# DE-290817_02.net
KiCad netlist of a schematic drawn in Altium Designer
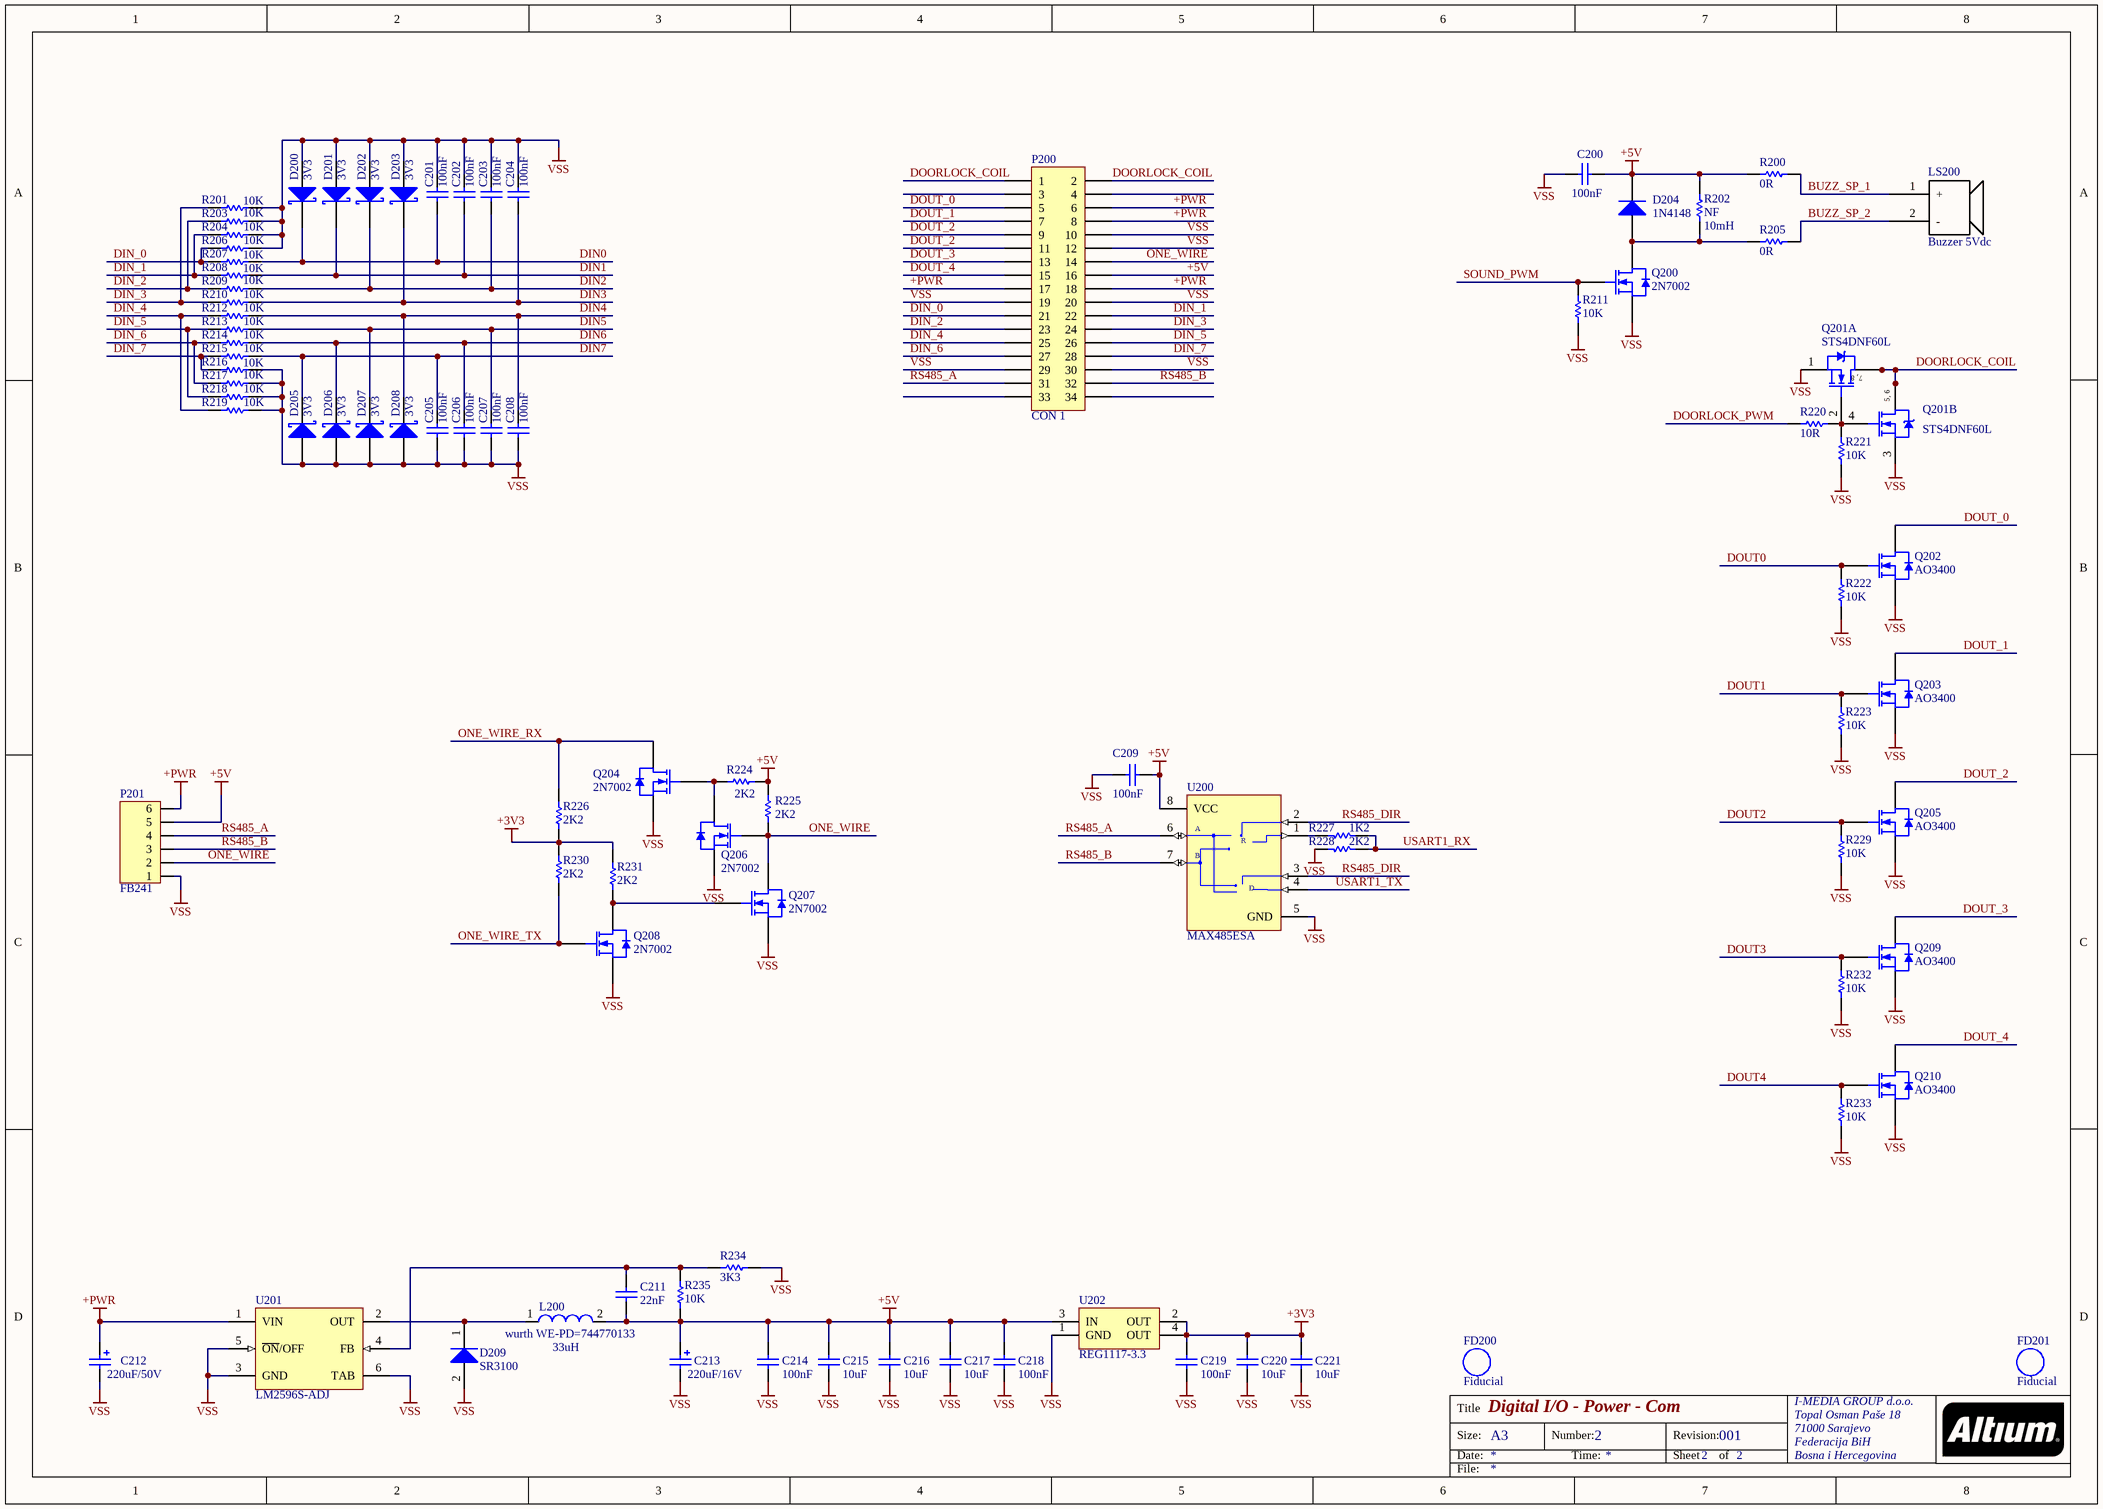
[diagram p0: DE-290817_02.SchDoc]

(export (version "E")
  (design (tool "Eeschema 10.0.6"))
  (components
    (comp (ref "C200")
      (value "100nF")
      (footprint "0603")
      (description "Ceramic Chip Capacitor - Standard")
      (fields (field (name "PUBLISHER") "Altium Limited"))
      (libsource (lib "DE-251215") (part "C0603"))
    )
    (comp (ref "C201")
      (value "100nF")
      (footprint "0603")
      (description "Ceramic Chip Capacitor - Standard")
      (fields (field (name "PUBLISHER") "Altium Limited"))
      (libsource (lib "DE-251215") (part "C0603"))
    )
    (comp (ref "C202")
      (value "100nF")
      (footprint "0603")
      (description "Ceramic Chip Capacitor - Standard")
      (fields (field (name "PUBLISHER") "Altium Limited"))
      (libsource (lib "DE-251215") (part "C0603"))
    )
    (comp (ref "C203")
      (value "100nF")
      (footprint "0603")
      (description "Ceramic Chip Capacitor - Standard")
      (fields (field (name "PUBLISHER") "Altium Limited"))
      (libsource (lib "DE-251215") (part "C0603"))
    )
    (comp (ref "C204")
      (value "100nF")
      (footprint "0603")
      (description "Ceramic Chip Capacitor - Standard")
      (fields (field (name "PUBLISHER") "Altium Limited"))
      (libsource (lib "DE-251215") (part "C0603"))
    )
    (comp (ref "C205")
      (value "100nF")
      (footprint "0603")
      (description "Ceramic Chip Capacitor - Standard")
      (fields (field (name "PUBLISHER") "Altium Limited"))
      (libsource (lib "DE-251215") (part "C0603"))
    )
    (comp (ref "C206")
      (value "100nF")
      (footprint "0603")
      (description "Ceramic Chip Capacitor - Standard")
      (fields (field (name "PUBLISHER") "Altium Limited"))
      (libsource (lib "DE-251215") (part "C0603"))
    )
    (comp (ref "C207")
      (value "100nF")
      (footprint "0603")
      (description "Ceramic Chip Capacitor - Standard")
      (fields (field (name "PUBLISHER") "Altium Limited"))
      (libsource (lib "DE-251215") (part "C0603"))
    )
    (comp (ref "C208")
      (value "100nF")
      (footprint "0603")
      (description "Ceramic Chip Capacitor - Standard")
      (fields (field (name "PUBLISHER") "Altium Limited"))
      (libsource (lib "DE-251215") (part "C0603"))
    )
    (comp (ref "C209")
      (value "100nF")
      (footprint "0603")
      (description "Ceramic Chip Capacitor - Standard")
      (fields (field (name "PUBLISHER") "Altium Limited"))
      (libsource (lib "DE-251215") (part "C0603"))
    )
    (comp (ref "C211")
      (value "22nF")
      (footprint "0603")
      (description "Ceramic Chip Capacitor - Standard")
      (fields (field (name "PUBLISHER") "Altium Limited"))
      (libsource (lib "DE-251215") (part "C0603"))
    )
    (comp (ref "C212")
      (value "220uF/50V")
      (footprint "EEEHA1H101P")
      (description "Aluminum Electrolytic Capacitors (SMD Type)")
      (libsource (lib "DE-290817") (part "EEEHA1H101P"))
    )
    (comp (ref "C213")
      (value "220uF/16V")
      (footprint "EEEHA1H101P")
      (description "Aluminum Electrolytic Capacitors (SMD Type)")
      (libsource (lib "DE-290817") (part "EEEHA1C221P"))
    )
    (comp (ref "C214")
      (value "100nF")
      (footprint "0603")
      (description "Ceramic Chip Capacitor - Standard")
      (fields (field (name "PUBLISHER") "Altium Limited"))
      (libsource (lib "DE-251215") (part "C0603"))
    )
    (comp (ref "C215")
      (value "10uF")
      (footprint "0805")
      (description "Ceramic Chip Capacitor - Standard")
      (fields (field (name "PUBLISHER") "Altium Limited"))
      (libsource (lib "DE-251215") (part "C0805"))
    )
    (comp (ref "C216")
      (value "10uF")
      (footprint "0805")
      (description "Ceramic Chip Capacitor - Standard")
      (fields (field (name "PUBLISHER") "Altium Limited"))
      (libsource (lib "DE-251215") (part "C0805"))
    )
    (comp (ref "C217")
      (value "10uF")
      (footprint "0805")
      (description "Ceramic Chip Capacitor - Standard")
      (fields (field (name "PUBLISHER") "Altium Limited"))
      (libsource (lib "DE-251215") (part "C0805"))
    )
    (comp (ref "C218")
      (value "100nF")
      (footprint "0603")
      (description "Ceramic Chip Capacitor - Standard")
      (fields (field (name "PUBLISHER") "Altium Limited"))
      (libsource (lib "DE-251215") (part "C0603"))
    )
    (comp (ref "C219")
      (value "100nF")
      (footprint "0603")
      (description "Ceramic Chip Capacitor - Standard")
      (fields (field (name "PUBLISHER") "Altium Limited"))
      (libsource (lib "DE-251215") (part "C0603"))
    )
    (comp (ref "C220")
      (value "10uF")
      (footprint "0805")
      (description "Ceramic Chip Capacitor - Standard")
      (fields (field (name "PUBLISHER") "Altium Limited"))
      (libsource (lib "DE-251215") (part "C0805"))
    )
    (comp (ref "C221")
      (value "10uF")
      (footprint "0805")
      (description "Ceramic Chip Capacitor - Standard")
      (fields (field (name "PUBLISHER") "Altium Limited"))
      (libsource (lib "DE-251215") (part "C0805"))
    )
    (comp (ref "D200")
      (value "3V3")
      (footprint "SOD323")
      (description "Schottky Barrier Diode")
      (fields (field (name "PUBLISHER") "Altium Limited"))
      (libsource (lib "DE-290817") (part "1PS76SB10"))
    )
    (comp (ref "D201")
      (value "3V3")
      (footprint "SOD323")
      (description "Schottky Barrier Diode")
      (fields (field (name "PUBLISHER") "Altium Limited"))
      (libsource (lib "DE-290817") (part "1PS76SB10"))
    )
    (comp (ref "D202")
      (value "3V3")
      (footprint "SOD323")
      (description "Schottky Barrier Diode")
      (fields (field (name "PUBLISHER") "Altium Limited"))
      (libsource (lib "DE-290817") (part "1PS76SB10"))
    )
    (comp (ref "D203")
      (value "3V3")
      (footprint "SOD323")
      (description "Schottky Barrier Diode")
      (fields (field (name "PUBLISHER") "Altium Limited"))
      (libsource (lib "DE-290817") (part "1PS76SB10"))
    )
    (comp (ref "D204")
      (value "1N4148")
      (footprint "SOD323")
      (description "General-purpose Diode")
      (fields (field (name "PUBLISHER") "Altium Limited"))
      (libsource (lib "DE-200216_01") (part "BAS321"))
    )
    (comp (ref "D205")
      (value "3V3")
      (footprint "SOD323")
      (description "Schottky Barrier Diode")
      (fields (field (name "PUBLISHER") "Altium Limited"))
      (libsource (lib "DE-290817") (part "1PS76SB10"))
    )
    (comp (ref "D206")
      (value "3V3")
      (footprint "SOD323")
      (description "Schottky Barrier Diode")
      (fields (field (name "PUBLISHER") "Altium Limited"))
      (libsource (lib "DE-290817") (part "1PS76SB10"))
    )
    (comp (ref "D207")
      (value "3V3")
      (footprint "SOD323")
      (description "Schottky Barrier Diode")
      (fields (field (name "PUBLISHER") "Altium Limited"))
      (libsource (lib "DE-290817") (part "1PS76SB10"))
    )
    (comp (ref "D208")
      (value "3V3")
      (footprint "SOD323")
      (description "Schottky Barrier Diode")
      (fields (field (name "PUBLISHER") "Altium Limited"))
      (libsource (lib "DE-290817") (part "1PS76SB10"))
    )
    (comp (ref "D209")
      (value "SR3100")
      (footprint "ONSC-SMA-2-403D-02_C_V")
      (description "Schottky Power Rectifier, 2-Pin SMA, Pb-Free, Tape and Reel")
      (fields (field (name "MANUFACTURER") "On Semiconductor") (field (name "PARTNUMBER") "MBRA320T3G"))
      (libsource (lib "ON Semi Schottky Diodes & Schottky Rectifiers") (part "MBRA320T3G"))
    )
    (comp (ref "FD200")
      (value "Fiducial")
      (footprint "Fiducial")
      (description "Fiduchial mark")
      (libsource (lib "DE-200216_02_1") (part "Fiduchial"))
    )
    (comp (ref "FD201")
      (value "Fiducial")
      (footprint "Fiducial")
      (description "Fiduchial mark")
      (libsource (lib "DE-200216_02_1") (part "Fiduchial"))
    )
    (comp (ref "L200")
      (value "wurth WE-PD=744770133")
      (footprint "WE-PD-XL")
      (description "SMD-Shielded Power Inductor WE-PD, L = 33 µH")
      (fields (field (name "PARTNUMBER") "744770133") (field (name "ALTIUM_VALUE") "33uH"))
      (libsource (lib "WE-PD SMD Shielded Power Inductor") (part "744770133"))
    )
    (comp (ref "LS200")
      (value "Buzzer 5Vdc")
      (footprint "BUZZER")
      (description "5Vdc PCB buzzer")
      (libsource (lib "DE-290817") (part "BUZZER"))
    )
    (comp (ref "P200")
      (value "CON 1")
      (footprint "HDR2X17")
      (description "Header, 17-Pin, Dual row")
      (fields (field (name "PUBLISHER") "Altium Limited"))
      (libsource (lib "Miscellaneous Connectors") (part "Header 17X2"))
    )
    (comp (ref "P201")
      (value "FB241")
      (footprint "FB241_6")
      (description "PCB MOUNT TERMINAL BLOCK 2.5MM PITCH")
      (libsource (lib "DE-290817") (part "TERMINAL BLOCK 6"))
    )
    (comp (ref "Q200")
      (value "2N7002")
      (footprint "SOT23_N")
      (description "N-channel Enhancement Mode Field-effect Transistor")
      (fields (field (name "PUBLISHER") "Altium Limited"))
      (libsource (lib "Philips Discrete MOSFET - Low Power") (part "2N7002"))
    )
    (comp (ref "Q201")
      (value "STS4DNF60L")
      (footprint "ONSC-SOIC-8-751-07_V")
      (description "Power MOSFET, 40 V, 5.8 A, Dual N-Channel, 8-Pin SOIC, Pb-Free, Tape and Reel")
      (fields (field (name "MANUFACTURER") "On Semiconductor") (field (name "PARTNUMBER") "NVMD6N04R2G"))
      (libsource (lib "ON Semi MOSFETs") (part "NVMD6N04R2G"))
    )
    (comp (ref "Q202")
      (value "AO3400")
      (footprint "SOT23_N")
      (description "N-channel Enhancement Mode Field-effect Transistor")
      (fields (field (name "PUBLISHER") "Altium Limited"))
      (libsource (lib "Philips Discrete MOSFET - Low Power") (part "2N7002"))
    )
    (comp (ref "Q203")
      (value "AO3400")
      (footprint "SOT23_N")
      (description "N-channel Enhancement Mode Field-effect Transistor")
      (fields (field (name "PUBLISHER") "Altium Limited"))
      (libsource (lib "Philips Discrete MOSFET - Low Power") (part "2N7002"))
    )
    (comp (ref "Q204")
      (value "2N7002")
      (footprint "SOT23_N")
      (description "N-channel Enhancement Mode Vertical D-MOSFET")
      (fields (field (name "PUBLISHER") "Altium Limited"))
      (libsource (lib "DE-290817") (part "BSS123"))
    )
    (comp (ref "Q205")
      (value "AO3400")
      (footprint "SOT23_N")
      (description "N-channel Enhancement Mode Field-effect Transistor")
      (fields (field (name "PUBLISHER") "Altium Limited"))
      (libsource (lib "Philips Discrete MOSFET - Low Power") (part "2N7002"))
    )
    (comp (ref "Q206")
      (value "2N7002")
      (footprint "SOT23_N")
      (description "N-channel Enhancement Mode Vertical D-MOSFET")
      (fields (field (name "PUBLISHER") "Altium Limited"))
      (libsource (lib "DE-290817") (part "BSS123"))
    )
    (comp (ref "Q207")
      (value "2N7002")
      (footprint "SOT23_N")
      (description "N-channel Enhancement Mode Vertical D-MOSFET")
      (fields (field (name "PUBLISHER") "Altium Limited"))
      (libsource (lib "DE-290817") (part "BSS123"))
    )
    (comp (ref "Q208")
      (value "2N7002")
      (footprint "SOT23_N")
      (description "N-channel Enhancement Mode Vertical D-MOSFET")
      (fields (field (name "PUBLISHER") "Altium Limited"))
      (libsource (lib "DE-290817") (part "BSS123"))
    )
    (comp (ref "Q209")
      (value "AO3400")
      (footprint "SOT23_N")
      (description "N-channel Enhancement Mode Field-effect Transistor")
      (fields (field (name "PUBLISHER") "Altium Limited"))
      (libsource (lib "Philips Discrete MOSFET - Low Power") (part "2N7002"))
    )
    (comp (ref "Q210")
      (value "AO3400")
      (footprint "SOT23_N")
      (description "N-channel Enhancement Mode Field-effect Transistor")
      (fields (field (name "PUBLISHER") "Altium Limited"))
      (libsource (lib "Philips Discrete MOSFET - Low Power") (part "2N7002"))
    )
    (comp (ref "R200")
      (value "0R")
      (footprint "ERA-0603")
      (fields (field (name "PUBLISHER") "Altium Limited"))
      (libsource (lib "DE-200216_03") (part "ERAV"))
    )
    (comp (ref "R201")
      (value "10K")
      (footprint "ERA-0603")
      (fields (field (name "PUBLISHER") "Altium Limited"))
      (libsource (lib "DE-200216_03") (part "ERAV"))
    )
    (comp (ref "R202")
      (value "NF")
      (footprint "RD3.2x1.7")
      (fields (field (name "ALTIUM_VALUE") "10mH") (field (name "PUBLISHER") "Altium Limited"))
      (libsource (lib "Panasonic Resistor") (part "ERD6FC"))
    )
    (comp (ref "R203")
      (value "10K")
      (footprint "ERA-0603")
      (fields (field (name "PUBLISHER") "Altium Limited"))
      (libsource (lib "DE-200216_03") (part "ERAV"))
    )
    (comp (ref "R204")
      (value "10K")
      (footprint "ERA-0603")
      (fields (field (name "PUBLISHER") "Altium Limited"))
      (libsource (lib "DE-251215") (part "ERAV"))
    )
    (comp (ref "R205")
      (value "0R")
      (footprint "ERA-0603")
      (fields (field (name "PUBLISHER") "Altium Limited"))
      (libsource (lib "DE-200216_03") (part "ERAV"))
    )
    (comp (ref "R206")
      (value "10K")
      (footprint "ERA-0603")
      (fields (field (name "PUBLISHER") "Altium Limited"))
      (libsource (lib "DE-251215") (part "ERAV"))
    )
    (comp (ref "R207")
      (value "10K")
      (footprint "ERA-0603")
      (fields (field (name "PUBLISHER") "Altium Limited"))
      (libsource (lib "DE-200216_03") (part "ERAV"))
    )
    (comp (ref "R208")
      (value "10K")
      (footprint "ERA-0603")
      (fields (field (name "PUBLISHER") "Altium Limited"))
      (libsource (lib "DE-200216_03") (part "ERAV"))
    )
    (comp (ref "R209")
      (value "10K")
      (footprint "ERA-0603")
      (fields (field (name "PUBLISHER") "Altium Limited"))
      (libsource (lib "DE-200216_03") (part "ERAV"))
    )
    (comp (ref "R210")
      (value "10K")
      (footprint "ERA-0603")
      (fields (field (name "PUBLISHER") "Altium Limited"))
      (libsource (lib "DE-251215") (part "ERAV"))
    )
    (comp (ref "R211")
      (value "10K")
      (footprint "ERA-0603")
      (fields (field (name "PUBLISHER") "Altium Limited"))
      (libsource (lib "DE-200216_03") (part "ERAV"))
    )
    (comp (ref "R212")
      (value "10K")
      (footprint "ERA-0603")
      (fields (field (name "PUBLISHER") "Altium Limited"))
      (libsource (lib "DE-251215") (part "ERAV"))
    )
    (comp (ref "R213")
      (value "10K")
      (footprint "ERA-0603")
      (fields (field (name "PUBLISHER") "Altium Limited"))
      (libsource (lib "DE-251215") (part "ERAV"))
    )
    (comp (ref "R214")
      (value "10K")
      (footprint "ERA-0603")
      (fields (field (name "PUBLISHER") "Altium Limited"))
      (libsource (lib "DE-251215") (part "ERAV"))
    )
    (comp (ref "R215")
      (value "10K")
      (footprint "ERA-0603")
      (fields (field (name "PUBLISHER") "Altium Limited"))
      (libsource (lib "DE-251215") (part "ERAV"))
    )
    (comp (ref "R216")
      (value "10K")
      (footprint "ERA-0603")
      (fields (field (name "PUBLISHER") "Altium Limited"))
      (libsource (lib "DE-200216_03") (part "ERAV"))
    )
    (comp (ref "R217")
      (value "10K")
      (footprint "ERA-0603")
      (fields (field (name "PUBLISHER") "Altium Limited"))
      (libsource (lib "DE-200216_03") (part "ERAV"))
    )
    (comp (ref "R218")
      (value "10K")
      (footprint "ERA-0603")
      (fields (field (name "PUBLISHER") "Altium Limited"))
      (libsource (lib "DE-251215") (part "ERAV"))
    )
    (comp (ref "R219")
      (value "10K")
      (footprint "ERA-0603")
      (fields (field (name "PUBLISHER") "Altium Limited"))
      (libsource (lib "DE-251215") (part "ERAV"))
    )
    (comp (ref "R220")
      (value "10R")
      (footprint "ERA-0603")
      (fields (field (name "PUBLISHER") "Altium Limited"))
      (libsource (lib "DE-200216_03") (part "ERAV"))
    )
    (comp (ref "R221")
      (value "10K")
      (footprint "ERA-0603")
      (fields (field (name "PUBLISHER") "Altium Limited"))
      (libsource (lib "DE-200216_03") (part "ERAV"))
    )
    (comp (ref "R222")
      (value "10K")
      (footprint "ERA-0603")
      (fields (field (name "PUBLISHER") "Altium Limited"))
      (libsource (lib "DE-200216_03") (part "ERAV"))
    )
    (comp (ref "R223")
      (value "10K")
      (footprint "ERA-0603")
      (fields (field (name "PUBLISHER") "Altium Limited"))
      (libsource (lib "DE-200216_03") (part "ERAV"))
    )
    (comp (ref "R224")
      (value "2K2")
      (footprint "ERA-0603")
      (fields (field (name "PUBLISHER") "Altium Limited"))
      (libsource (lib "DE-200216_03") (part "ERAV"))
    )
    (comp (ref "R225")
      (value "2K2")
      (footprint "ERA-0603")
      (fields (field (name "PUBLISHER") "Altium Limited"))
      (libsource (lib "DE-200216_03") (part "ERAV"))
    )
    (comp (ref "R226")
      (value "2K2")
      (footprint "ERA-0603")
      (fields (field (name "PUBLISHER") "Altium Limited"))
      (libsource (lib "DE-290817") (part "ERAV"))
    )
    (comp (ref "R227")
      (value "1K2")
      (footprint "ERA-0603")
      (fields (field (name "PUBLISHER") "Altium Limited"))
      (libsource (lib "DE-200216_03") (part "ERAV"))
    )
    (comp (ref "R228")
      (value "2K2")
      (footprint "ERA-0603")
      (fields (field (name "PUBLISHER") "Altium Limited"))
      (libsource (lib "DE-200216_03") (part "ERAV"))
    )
    (comp (ref "R229")
      (value "10K")
      (footprint "ERA-0603")
      (fields (field (name "PUBLISHER") "Altium Limited"))
      (libsource (lib "DE-200216_03") (part "ERAV"))
    )
    (comp (ref "R230")
      (value "2K2")
      (footprint "ERA-0603")
      (fields (field (name "PUBLISHER") "Altium Limited"))
      (libsource (lib "DE-200216_03") (part "ERAV"))
    )
    (comp (ref "R231")
      (value "2K2")
      (footprint "ERA-0603")
      (fields (field (name "PUBLISHER") "Altium Limited"))
      (libsource (lib "DE-200216_03") (part "ERAV"))
    )
    (comp (ref "R232")
      (value "10K")
      (footprint "ERA-0603")
      (fields (field (name "PUBLISHER") "Altium Limited"))
      (libsource (lib "DE-200216_03") (part "ERAV"))
    )
    (comp (ref "R233")
      (value "10K")
      (footprint "ERA-0603")
      (fields (field (name "PUBLISHER") "Altium Limited"))
      (libsource (lib "DE-200216_03") (part "ERAV"))
    )
    (comp (ref "R234")
      (value "3K3")
      (footprint "ERA-0603")
      (fields (field (name "PUBLISHER") "Altium Limited"))
      (libsource (lib "DE-251215") (part "ERAV"))
    )
    (comp (ref "R235")
      (value "10K")
      (footprint "ERA-0603")
      (fields (field (name "PUBLISHER") "Altium Limited"))
      (libsource (lib "DE-251215") (part "ERAV"))
    )
    (comp (ref "U200")
      (value "MAX485ESA")
      (footprint "NSO8_M")
      (description "Low-Power, Slew-Rate-Limited RS-485/RS-422 Transceiver")
      (fields (field (name "PUBLISHER") "Altium Limited"))
      (libsource (lib "Maxim Communication Transceiver") (part "MAX485ESA"))
    )
    (comp (ref "U201")
      (value "LM2596S-ADJ")
      (footprint "TS5B_N")
      (description "SIMPLE SWITCHER® Power Converter 150 KHz 3A Step-Down Voltage Regulator, 5-pin TO-263")
      (fields (field (name "MANUFACTURER") "National Semiconductor"))
      (libsource (lib "National Semiconductor Switcher") (part "LM2596S-ADJ"))
    )
    (comp (ref "U202")
      (value "REG1117-3.3")
      (footprint "ZZ311")
      (description "800mA and 1A Low Dropout Positive Regulator 2.85V, 3.3V, 5V, and Adjustable")
      (fields (field (name "PUBLISHER") "Altium Limited"))
      (libsource (lib "DE-251215") (part "REG1117-3.3"))
    )
  )
  (nets
    (net (code "1") (name "+3V3") (class "Default")
      (node (ref "C219") (pin "2") (pinfunction "2_2") (pintype "passive"))
      (node (ref "C220") (pin "2") (pinfunction "2_2") (pintype "passive"))
      (node (ref "C221") (pin "2") (pinfunction "2_2") (pintype "passive"))
      (node (ref "R226") (pin "1") (pinfunction "1_1") (pintype "passive"))
      (node (ref "R230") (pin "2") (pinfunction "2_2") (pintype "passive"))
      (node (ref "R231") (pin "2") (pinfunction "2_2") (pintype "passive"))
      (node (ref "U202") (pin "2") (pinfunction "OUT_2") (pintype "power_in"))
      (node (ref "U202") (pin "4") (pinfunction "OUT_4") (pintype "power_in"))
    )
    (net (code "2") (name "+5V") (class "Default")
      (node (ref "C200") (pin "1") (pinfunction "1_1") (pintype "passive"))
      (node (ref "C209") (pin "2") (pinfunction "2_2") (pintype "passive"))
      (node (ref "C211") (pin "1") (pinfunction "1_1") (pintype "passive"))
      (node (ref "C213") (pin "1") (pinfunction "1_1") (pintype "passive"))
      (node (ref "C214") (pin "2") (pinfunction "2_2") (pintype "passive"))
      (node (ref "C215") (pin "2") (pinfunction "2_2") (pintype "passive"))
      (node (ref "C216") (pin "2") (pinfunction "2_2") (pintype "passive"))
      (node (ref "C217") (pin "2") (pinfunction "2_2") (pintype "passive"))
      (node (ref "C218") (pin "2") (pinfunction "2_2") (pintype "passive"))
      (node (ref "D204") (pin "1") (pinfunction "K_1") (pintype "passive"))
      (node (ref "L200") (pin "2") (pinfunction "2_2") (pintype "passive"))
      (node (ref "P200") (pin "16") (pinfunction "16_16") (pintype "passive"))
      (node (ref "P201") (pin "5") (pinfunction "5_5") (pintype "passive"))
      (node (ref "R200") (pin "2") (pinfunction "2_2") (pintype "passive"))
      (node (ref "R202") (pin "2") (pinfunction "2_2") (pintype "passive"))
      (node (ref "R224") (pin "1") (pinfunction "1_1") (pintype "passive"))
      (node (ref "R225") (pin "2") (pinfunction "2_2") (pintype "passive"))
      (node (ref "R235") (pin "2") (pinfunction "2_2") (pintype "passive"))
      (node (ref "U200") (pin "8") (pinfunction "VCC_8") (pintype "power_in"))
      (node (ref "U202") (pin "3") (pinfunction "IN_3") (pintype "power_in"))
    )
    (net (code "3") (name "+PWR") (class "Default")
      (node (ref "C212") (pin "1") (pinfunction "1_1") (pintype "passive"))
      (node (ref "P200") (pin "17") (pinfunction "17_17") (pintype "passive"))
      (node (ref "P200") (pin "18") (pinfunction "18_18") (pintype "passive"))
      (node (ref "P200") (pin "6") (pinfunction "6_6") (pintype "passive"))
      (node (ref "P200") (pin "8") (pinfunction "8_8") (pintype "passive"))
      (node (ref "P201") (pin "6") (pinfunction "6_6") (pintype "passive"))
      (node (ref "U201") (pin "1") (pinfunction "VIN_1") (pintype "power_in"))
    )
    (net (code "4") (name "/BUZZ_SP_1") (class "Default")
      (node (ref "LS200") (pin "1") (pinfunction "+_1") (pintype "passive"))
      (node (ref "R200") (pin "1") (pinfunction "1_1") (pintype "passive"))
    )
    (net (code "5") (name "/BUZZ_SP_2") (class "Default")
      (node (ref "LS200") (pin "2") (pinfunction "-_2") (pintype "passive"))
      (node (ref "R205") (pin "1") (pinfunction "1_1") (pintype "passive"))
    )
    (net (code "6") (name "/DIN0") (class "Default")
      (node (ref "C201") (pin "2") (pinfunction "2_2") (pintype "passive"))
      (node (ref "D200") (pin "1") (pinfunction "K_1") (pintype "passive"))
      (node (ref "R207") (pin "2") (pinfunction "2_2") (pintype "passive"))
    )
    (net (code "7") (name "/DIN1") (class "Default")
      (node (ref "C202") (pin "2") (pinfunction "2_2") (pintype "passive"))
      (node (ref "D201") (pin "1") (pinfunction "K_1") (pintype "passive"))
      (node (ref "R208") (pin "2") (pinfunction "2_2") (pintype "passive"))
    )
    (net (code "8") (name "/DIN2") (class "Default")
      (node (ref "C203") (pin "2") (pinfunction "2_2") (pintype "passive"))
      (node (ref "D202") (pin "1") (pinfunction "K_1") (pintype "passive"))
      (node (ref "R209") (pin "2") (pinfunction "2_2") (pintype "passive"))
    )
    (net (code "9") (name "/DIN3") (class "Default")
      (node (ref "C204") (pin "2") (pinfunction "2_2") (pintype "passive"))
      (node (ref "D203") (pin "1") (pinfunction "K_1") (pintype "passive"))
      (node (ref "R210") (pin "2") (pinfunction "2_2") (pintype "passive"))
    )
    (net (code "10") (name "/DIN4") (class "Default")
      (node (ref "C208") (pin "2") (pinfunction "2_2") (pintype "passive"))
      (node (ref "D208") (pin "1") (pinfunction "K_1") (pintype "passive"))
      (node (ref "R212") (pin "2") (pinfunction "2_2") (pintype "passive"))
    )
    (net (code "11") (name "/DIN5") (class "Default")
      (node (ref "C207") (pin "2") (pinfunction "2_2") (pintype "passive"))
      (node (ref "D207") (pin "1") (pinfunction "K_1") (pintype "passive"))
      (node (ref "R213") (pin "2") (pinfunction "2_2") (pintype "passive"))
    )
    (net (code "12") (name "/DIN6") (class "Default")
      (node (ref "C206") (pin "2") (pinfunction "2_2") (pintype "passive"))
      (node (ref "D206") (pin "1") (pinfunction "K_1") (pintype "passive"))
      (node (ref "R214") (pin "2") (pinfunction "2_2") (pintype "passive"))
    )
    (net (code "13") (name "/DIN7") (class "Default")
      (node (ref "C205") (pin "2") (pinfunction "2_2") (pintype "passive"))
      (node (ref "D205") (pin "1") (pinfunction "K_1") (pintype "passive"))
      (node (ref "R215") (pin "2") (pinfunction "2_2") (pintype "passive"))
    )
    (net (code "14") (name "/DIN_0") (class "Default")
      (node (ref "P200") (pin "21") (pinfunction "21_21") (pintype "passive"))
      (node (ref "R206") (pin "1") (pinfunction "1_1") (pintype "passive"))
      (node (ref "R207") (pin "1") (pinfunction "1_1") (pintype "passive"))
    )
    (net (code "15") (name "/DIN_1") (class "Default")
      (node (ref "P200") (pin "22") (pinfunction "22_22") (pintype "passive"))
      (node (ref "R204") (pin "1") (pinfunction "1_1") (pintype "passive"))
      (node (ref "R208") (pin "1") (pinfunction "1_1") (pintype "passive"))
    )
    (net (code "16") (name "/DIN_2") (class "Default")
      (node (ref "P200") (pin "23") (pinfunction "23_23") (pintype "passive"))
      (node (ref "R203") (pin "1") (pinfunction "1_1") (pintype "passive"))
      (node (ref "R209") (pin "1") (pinfunction "1_1") (pintype "passive"))
    )
    (net (code "17") (name "/DIN_3") (class "Default")
      (node (ref "P200") (pin "24") (pinfunction "24_24") (pintype "passive"))
      (node (ref "R201") (pin "1") (pinfunction "1_1") (pintype "passive"))
      (node (ref "R210") (pin "1") (pinfunction "1_1") (pintype "passive"))
    )
    (net (code "18") (name "/DIN_4") (class "Default")
      (node (ref "P200") (pin "25") (pinfunction "25_25") (pintype "passive"))
      (node (ref "R212") (pin "1") (pinfunction "1_1") (pintype "passive"))
      (node (ref "R219") (pin "1") (pinfunction "1_1") (pintype "passive"))
    )
    (net (code "19") (name "/DIN_5") (class "Default")
      (node (ref "P200") (pin "26") (pinfunction "26_26") (pintype "passive"))
      (node (ref "R213") (pin "1") (pinfunction "1_1") (pintype "passive"))
      (node (ref "R218") (pin "1") (pinfunction "1_1") (pintype "passive"))
    )
    (net (code "20") (name "/DIN_6") (class "Default")
      (node (ref "P200") (pin "27") (pinfunction "27_27") (pintype "passive"))
      (node (ref "R214") (pin "1") (pinfunction "1_1") (pintype "passive"))
      (node (ref "R217") (pin "1") (pinfunction "1_1") (pintype "passive"))
    )
    (net (code "21") (name "/DIN_7") (class "Default")
      (node (ref "P200") (pin "28") (pinfunction "28_28") (pintype "passive"))
      (node (ref "R215") (pin "1") (pinfunction "1_1") (pintype "passive"))
      (node (ref "R216") (pin "1") (pinfunction "1_1") (pintype "passive"))
    )
    (net (code "22") (name "/DOORLOCK_COIL") (class "Default")
      (node (ref "P200") (pin "1") (pinfunction "1_1") (pintype "passive"))
      (node (ref "P200") (pin "2") (pinfunction "2_2") (pintype "passive"))
      (node (ref "Q201") (pin "5") (pinfunction "D2_5") (pintype "passive"))
      (node (ref "Q201") (pin "6") (pinfunction "D2_6") (pintype "passive"))
      (node (ref "Q201") (pin "7") (pinfunction "D1_7") (pintype "passive"))
      (node (ref "Q201") (pin "8") (pinfunction "D1_8") (pintype "passive"))
    )
    (net (code "23") (name "/DOORLOCK_PWM") (class "Default")
      (node (ref "R220") (pin "2") (pinfunction "2_2") (pintype "passive"))
    )
    (net (code "24") (name "/DOUT0") (class "Default")
      (node (ref "Q202") (pin "1") (pinfunction "G_1") (pintype "passive"))
      (node (ref "R222") (pin "2") (pinfunction "2_2") (pintype "passive"))
    )
    (net (code "25") (name "/DOUT1") (class "Default")
      (node (ref "Q203") (pin "1") (pinfunction "G_1") (pintype "passive"))
      (node (ref "R223") (pin "2") (pinfunction "2_2") (pintype "passive"))
    )
    (net (code "26") (name "/DOUT2") (class "Default")
      (node (ref "Q205") (pin "1") (pinfunction "G_1") (pintype "passive"))
      (node (ref "R229") (pin "2") (pinfunction "2_2") (pintype "passive"))
    )
    (net (code "27") (name "/DOUT3") (class "Default")
      (node (ref "Q209") (pin "1") (pinfunction "G_1") (pintype "passive"))
      (node (ref "R232") (pin "2") (pinfunction "2_2") (pintype "passive"))
    )
    (net (code "28") (name "/DOUT4") (class "Default")
      (node (ref "Q210") (pin "1") (pinfunction "G_1") (pintype "passive"))
      (node (ref "R233") (pin "2") (pinfunction "2_2") (pintype "passive"))
    )
    (net (code "29") (name "/DOUT_0") (class "Default")
      (node (ref "P200") (pin "5") (pinfunction "5_5") (pintype "passive"))
      (node (ref "Q202") (pin "3") (pinfunction "D_3") (pintype "passive"))
    )
    (net (code "30") (name "/DOUT_1") (class "Default")
      (node (ref "P200") (pin "7") (pinfunction "7_7") (pintype "passive"))
      (node (ref "Q203") (pin "3") (pinfunction "D_3") (pintype "passive"))
    )
    (net (code "31") (name "/DOUT_2") (class "Default")
      (node (ref "P200") (pin "11") (pinfunction "11_11") (pintype "passive"))
      (node (ref "P200") (pin "9") (pinfunction "9_9") (pintype "passive"))
      (node (ref "Q205") (pin "3") (pinfunction "D_3") (pintype "passive"))
    )
    (net (code "32") (name "/DOUT_3") (class "Default")
      (node (ref "P200") (pin "13") (pinfunction "13_13") (pintype "passive"))
      (node (ref "Q209") (pin "3") (pinfunction "D_3") (pintype "passive"))
    )
    (net (code "33") (name "/DOUT_4") (class "Default")
      (node (ref "P200") (pin "15") (pinfunction "15_15") (pintype "passive"))
      (node (ref "Q210") (pin "3") (pinfunction "D_3") (pintype "passive"))
    )
    (net (code "34") (name "/ONE_WIRE") (class "Default")
      (node (ref "P200") (pin "14") (pinfunction "14_14") (pintype "passive"))
      (node (ref "P201") (pin "2") (pinfunction "2_2") (pintype "passive"))
      (node (ref "Q206") (pin "1") (pinfunction "G_1") (pintype "passive"))
      (node (ref "Q207") (pin "3") (pinfunction "D_3") (pintype "passive"))
      (node (ref "R225") (pin "1") (pinfunction "1_1") (pintype "passive"))
    )
    (net (code "35") (name "/ONE_WIRE_RX") (class "Default")
      (node (ref "Q204") (pin "3") (pinfunction "D_3") (pintype "passive"))
      (node (ref "R226") (pin "2") (pinfunction "2_2") (pintype "passive"))
    )
    (net (code "36") (name "/ONE_WIRE_TX") (class "Default")
      (node (ref "Q208") (pin "1") (pinfunction "G_1") (pintype "passive"))
      (node (ref "R230") (pin "1") (pinfunction "1_1") (pintype "passive"))
    )
    (net (code "37") (name "/RS485_A") (class "Default")
      (node (ref "P200") (pin "31") (pinfunction "31_31") (pintype "passive"))
      (node (ref "P201") (pin "4") (pinfunction "4_4") (pintype "passive"))
      (node (ref "U200") (pin "6") (pinfunction "A_6") (pintype "bidirectional"))
    )
    (net (code "38") (name "/RS485_B") (class "Default")
      (node (ref "P200") (pin "32") (pinfunction "32_32") (pintype "passive"))
      (node (ref "P201") (pin "3") (pinfunction "3_3") (pintype "passive"))
      (node (ref "U200") (pin "7") (pinfunction "B_7") (pintype "bidirectional"))
    )
    (net (code "39") (name "/RS485_DIR") (class "Default")
      (node (ref "U200") (pin "2") (pinfunction "~{RE}_2") (pintype "input"))
      (node (ref "U200") (pin "3") (pinfunction "DE_3") (pintype "input"))
    )
    (net (code "40") (name "/SOUND_PWM") (class "Default")
      (node (ref "Q200") (pin "1") (pinfunction "G_1") (pintype "passive"))
      (node (ref "R211") (pin "2") (pinfunction "2_2") (pintype "passive"))
    )
    (net (code "41") (name "/USART1_RX") (class "Default")
      (node (ref "R227") (pin "2") (pinfunction "2_2") (pintype "passive"))
      (node (ref "R228") (pin "1") (pinfunction "1_1") (pintype "passive"))
    )
    (net (code "42") (name "/USART1_TX") (class "Default")
      (node (ref "U200") (pin "4") (pinfunction "DI_4") (pintype "input"))
    )
    (net (code "43") (name "Net-(D204-A)") (class "Default")
      (node (ref "D204") (pin "2") (pinfunction "A_2") (pintype "passive"))
      (node (ref "Q200") (pin "3") (pinfunction "D_3") (pintype "passive"))
      (node (ref "R202") (pin "1") (pinfunction "1_1") (pintype "passive"))
      (node (ref "R205") (pin "2") (pinfunction "2_2") (pintype "passive"))
    )
    (net (code "44") (name "Net-(D209-K)") (class "Default")
      (node (ref "D209") (pin "1") (pinfunction "K_1") (pintype "passive"))
      (node (ref "L200") (pin "1") (pinfunction "1_1") (pintype "passive"))
      (node (ref "U201") (pin "2") (pinfunction "OUT_2") (pintype "power_in"))
    )
    (net (code "45") (name "Net-(Q201A-G1)") (class "Default")
      (node (ref "Q201") (pin "2") (pinfunction "G1_2") (pintype "passive"))
      (node (ref "Q201") (pin "4") (pinfunction "G2_4") (pintype "passive"))
      (node (ref "R220") (pin "1") (pinfunction "1_1") (pintype "passive"))
      (node (ref "R221") (pin "1") (pinfunction "1_1") (pintype "passive"))
    )
    (net (code "46") (name "Net-(Q204-G)") (class "Default")
      (node (ref "Q204") (pin "1") (pinfunction "G_1") (pintype "passive"))
      (node (ref "Q206") (pin "3") (pinfunction "D_3") (pintype "passive"))
      (node (ref "R224") (pin "2") (pinfunction "2_2") (pintype "passive"))
    )
    (net (code "47") (name "Net-(Q207-G)") (class "Default")
      (node (ref "Q207") (pin "1") (pinfunction "G_1") (pintype "passive"))
      (node (ref "Q208") (pin "3") (pinfunction "D_3") (pintype "passive"))
      (node (ref "R231") (pin "1") (pinfunction "1_1") (pintype "passive"))
    )
    (net (code "48") (name "Net-(U200-RO)") (class "Default")
      (node (ref "R227") (pin "1") (pinfunction "1_1") (pintype "passive"))
      (node (ref "U200") (pin "1") (pinfunction "RO_1") (pintype "output"))
    )
    (net (code "49") (name "Net-(U201-FB)") (class "Default")
      (node (ref "C211") (pin "2") (pinfunction "2_2") (pintype "passive"))
      (node (ref "R234") (pin "1") (pinfunction "1_1") (pintype "passive"))
      (node (ref "R235") (pin "1") (pinfunction "1_1") (pintype "passive"))
      (node (ref "U201") (pin "4") (pinfunction "FB_4") (pintype "input"))
    )
    (net (code "50") (name "VSS") (class "Default")
      (node (ref "C200") (pin "2") (pinfunction "2_2") (pintype "passive"))
      (node (ref "C201") (pin "1") (pinfunction "1_1") (pintype "passive"))
      (node (ref "C202") (pin "1") (pinfunction "1_1") (pintype "passive"))
      (node (ref "C203") (pin "1") (pinfunction "1_1") (pintype "passive"))
      (node (ref "C204") (pin "1") (pinfunction "1_1") (pintype "passive"))
      (node (ref "C205") (pin "1") (pinfunction "1_1") (pintype "passive"))
      (node (ref "C206") (pin "1") (pinfunction "1_1") (pintype "passive"))
      (node (ref "C207") (pin "1") (pinfunction "1_1") (pintype "passive"))
      (node (ref "C208") (pin "1") (pinfunction "1_1") (pintype "passive"))
      (node (ref "C209") (pin "1") (pinfunction "1_1") (pintype "passive"))
      (node (ref "C212") (pin "2") (pinfunction "2_2") (pintype "passive"))
      (node (ref "C213") (pin "2") (pinfunction "2_2") (pintype "passive"))
      (node (ref "C214") (pin "1") (pinfunction "1_1") (pintype "passive"))
      (node (ref "C215") (pin "1") (pinfunction "1_1") (pintype "passive"))
      (node (ref "C216") (pin "1") (pinfunction "1_1") (pintype "passive"))
      (node (ref "C217") (pin "1") (pinfunction "1_1") (pintype "passive"))
      (node (ref "C218") (pin "1") (pinfunction "1_1") (pintype "passive"))
      (node (ref "C219") (pin "1") (pinfunction "1_1") (pintype "passive"))
      (node (ref "C220") (pin "1") (pinfunction "1_1") (pintype "passive"))
      (node (ref "C221") (pin "1") (pinfunction "1_1") (pintype "passive"))
      (node (ref "D200") (pin "2") (pinfunction "A_2") (pintype "passive"))
      (node (ref "D201") (pin "2") (pinfunction "A_2") (pintype "passive"))
      (node (ref "D202") (pin "2") (pinfunction "A_2") (pintype "passive"))
      (node (ref "D203") (pin "2") (pinfunction "A_2") (pintype "passive"))
      (node (ref "D205") (pin "2") (pinfunction "A_2") (pintype "passive"))
      (node (ref "D206") (pin "2") (pinfunction "A_2") (pintype "passive"))
      (node (ref "D207") (pin "2") (pinfunction "A_2") (pintype "passive"))
      (node (ref "D208") (pin "2") (pinfunction "A_2") (pintype "passive"))
      (node (ref "D209") (pin "2") (pinfunction "A_2") (pintype "passive"))
      (node (ref "P200") (pin "10") (pinfunction "10_10") (pintype "passive"))
      (node (ref "P200") (pin "12") (pinfunction "12_12") (pintype "passive"))
      (node (ref "P200") (pin "19") (pinfunction "19_19") (pintype "passive"))
      (node (ref "P200") (pin "20") (pinfunction "20_20") (pintype "passive"))
      (node (ref "P200") (pin "29") (pinfunction "29_29") (pintype "passive"))
      (node (ref "P200") (pin "30") (pinfunction "30_30") (pintype "passive"))
      (node (ref "P201") (pin "1") (pinfunction "1_1") (pintype "passive"))
      (node (ref "Q200") (pin "2") (pinfunction "S_2") (pintype "passive"))
      (node (ref "Q201") (pin "1") (pinfunction "S1_1") (pintype "passive"))
      (node (ref "Q201") (pin "3") (pinfunction "S2_3") (pintype "passive"))
      (node (ref "Q202") (pin "2") (pinfunction "S_2") (pintype "passive"))
      (node (ref "Q203") (pin "2") (pinfunction "S_2") (pintype "passive"))
      (node (ref "Q204") (pin "2") (pinfunction "S_2") (pintype "passive"))
      (node (ref "Q205") (pin "2") (pinfunction "S_2") (pintype "passive"))
      (node (ref "Q206") (pin "2") (pinfunction "S_2") (pintype "passive"))
      (node (ref "Q207") (pin "2") (pinfunction "S_2") (pintype "passive"))
      (node (ref "Q208") (pin "2") (pinfunction "S_2") (pintype "passive"))
      (node (ref "Q209") (pin "2") (pinfunction "S_2") (pintype "passive"))
      (node (ref "Q210") (pin "2") (pinfunction "S_2") (pintype "passive"))
      (node (ref "R201") (pin "2") (pinfunction "2_2") (pintype "passive"))
      (node (ref "R203") (pin "2") (pinfunction "2_2") (pintype "passive"))
      (node (ref "R204") (pin "2") (pinfunction "2_2") (pintype "passive"))
      (node (ref "R206") (pin "2") (pinfunction "2_2") (pintype "passive"))
      (node (ref "R211") (pin "1") (pinfunction "1_1") (pintype "passive"))
      (node (ref "R216") (pin "2") (pinfunction "2_2") (pintype "passive"))
      (node (ref "R217") (pin "2") (pinfunction "2_2") (pintype "passive"))
      (node (ref "R218") (pin "2") (pinfunction "2_2") (pintype "passive"))
      (node (ref "R219") (pin "2") (pinfunction "2_2") (pintype "passive"))
      (node (ref "R221") (pin "2") (pinfunction "2_2") (pintype "passive"))
      (node (ref "R222") (pin "1") (pinfunction "1_1") (pintype "passive"))
      (node (ref "R223") (pin "1") (pinfunction "1_1") (pintype "passive"))
      (node (ref "R228") (pin "2") (pinfunction "2_2") (pintype "passive"))
      (node (ref "R229") (pin "1") (pinfunction "1_1") (pintype "passive"))
      (node (ref "R232") (pin "1") (pinfunction "1_1") (pintype "passive"))
      (node (ref "R233") (pin "1") (pinfunction "1_1") (pintype "passive"))
      (node (ref "R234") (pin "2") (pinfunction "2_2") (pintype "passive"))
      (node (ref "U200") (pin "5") (pinfunction "GND_5") (pintype "power_in"))
      (node (ref "U201") (pin "3") (pinfunction "GND_3") (pintype "power_in"))
      (node (ref "U201") (pin "5") (pinfunction "~{ON}/OFF_5") (pintype "input"))
      (node (ref "U201") (pin "6") (pinfunction "TAB_6") (pintype "power_in"))
      (node (ref "U202") (pin "1") (pinfunction "GND_1") (pintype "power_in"))
    )
    (net (code "51") (name "unconnected-(P200-Pad3)") (class "Default")
      (node (ref "P200") (pin "3") (pinfunction "3_3") (pintype "passive"))
    )
    (net (code "52") (name "unconnected-(P200-Pad4)") (class "Default")
      (node (ref "P200") (pin "4") (pinfunction "4_4") (pintype "passive"))
    )
    (net (code "53") (name "unconnected-(P200-Pad33)") (class "Default")
      (node (ref "P200") (pin "33") (pinfunction "33_33") (pintype "passive"))
    )
    (net (code "54") (name "unconnected-(P200-Pad34)") (class "Default")
      (node (ref "P200") (pin "34") (pinfunction "34_34") (pintype "passive"))
    )
  )
)
